# Sheet1.net
KiCad netlist of a schematic drawn in Altium Designer
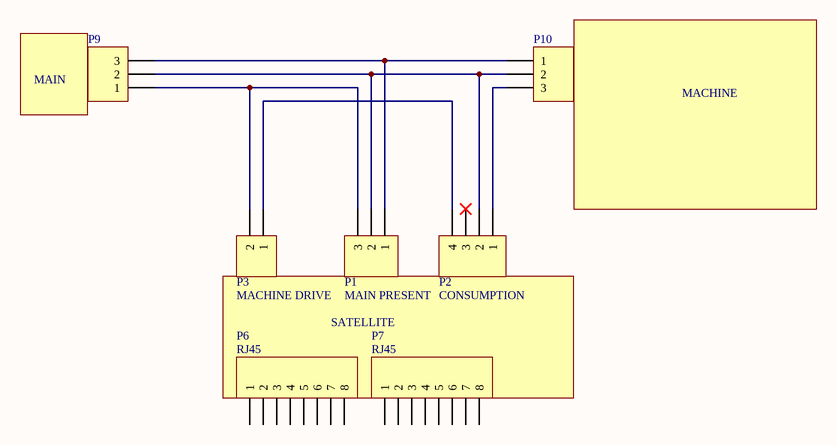
[diagram p0: Sheet1.SchDoc]

(export (version "E")
  (design (tool "Eeschema 10.0.6"))
  (components
    (comp (ref "P1")
      (value "MAIN PRESENT")
      (footprint "CO3P508")
      (description "Header, 3-Pin")
      (fields
        (field (name "MANUFACTURER") "TE CONNECTIVITY / BUCHANAN")
        (field (name "MANUFACTURER PART NUMBER") "796636-3")
      )
      (libsource (lib "Miscellaneous Connectors") (part "Header 3"))
    )
    (comp (ref "P2")
      (value "CONSUMPTION")
      (footprint "CO4P508")
      (description "Header, 4-Pin")
      (fields
        (field (name "MANUFACTURER") "TE CONNECTIVITY / BUCHANAN")
        (field (name "MANUFACTURER PART NUMBER") "796636-4")
      )
      (libsource (lib "Miscellaneous Connectors") (part "Header 4"))
    )
    (comp (ref "P3")
      (value "MACHINE DRIVE")
      (footprint "CO2P508")
      (description "Header, 2-Pin")
      (fields
        (field (name "MANUFACTURER") "TE CONNECTIVITY / BUCHANAN")
        (field (name "MANUFACTURER PART NUMBER") "796636-2")
      )
      (libsource (lib "Miscellaneous Connectors") (part "Header 2"))
    )
    (comp (ref "P6")
      (value "RJ45")
      (footprint "SYLANN:Amphenol-RJ45_8")
      (description "Header, 8-Pin")
      (fields (field (name "MANUFACTURER") "MOLEX") (field (name "MANUFACTURER PART NUMBER") "85502-5008"))
      (libsource (lib "Miscellaneous Connectors") (part "Header 8"))
    )
    (comp (ref "P7")
      (value "RJ45")
      (footprint "SYLANN:Amphenol-RJ45_8")
      (description "Header, 8-Pin")
      (fields (field (name "MANUFACTURER") "MOLEX") (field (name "MANUFACTURER PART NUMBER") "85502-5008"))
      (libsource (lib "Miscellaneous Connectors") (part "Header 8"))
    )
    (comp (ref "P9")
      (value "Header 3")
      (footprint "HDR1X3")
      (description "Header, 3-Pin")
      (fields (field (name "PUBLISHER") "Altium Limited"))
      (libsource (lib "") (part "Header 3_1"))
    )
    (comp (ref "P10")
      (value "Header 3")
      (footprint "HDR1X3")
      (description "Header, 3-Pin")
      (fields (field (name "PUBLISHER") "Altium Limited"))
      (libsource (lib "") (part "Header 3_2"))
    )
  )
  (nets
    (net (code "1") (name "Net-(P1-Pad1)") (class "Default")
      (node (ref "P1") (pin "1") (pinfunction "1_1") (pintype "passive"))
      (node (ref "P10") (pin "1") (pinfunction "1_1") (pintype "passive"))
      (node (ref "P9") (pin "3") (pinfunction "3_3") (pintype "passive"))
    )
    (net (code "2") (name "Net-(P1-Pad2)") (class "Default")
      (node (ref "P1") (pin "2") (pinfunction "2_2") (pintype "passive"))
      (node (ref "P10") (pin "2") (pinfunction "2_2") (pintype "passive"))
      (node (ref "P2") (pin "2") (pinfunction "2_2") (pintype "passive"))
      (node (ref "P9") (pin "2") (pinfunction "2_2") (pintype "passive"))
    )
    (net (code "3") (name "Net-(P1-Pad3)") (class "Default")
      (node (ref "P1") (pin "3") (pinfunction "3_3") (pintype "passive"))
      (node (ref "P3") (pin "2") (pinfunction "2_2") (pintype "passive"))
      (node (ref "P9") (pin "1") (pinfunction "1_1") (pintype "passive"))
    )
    (net (code "4") (name "Net-(P2-Pad4)") (class "Default")
      (node (ref "P2") (pin "4") (pinfunction "4_4") (pintype "passive"))
      (node (ref "P3") (pin "1") (pinfunction "1_1") (pintype "passive"))
    )
    (net (code "5") (name "Net-(P10-Pad3)") (class "Default")
      (node (ref "P10") (pin "3") (pinfunction "3_3") (pintype "passive"))
      (node (ref "P2") (pin "1") (pinfunction "1_1") (pintype "passive"))
    )
    (net (code "6") (name "unconnected-(P2-Pad3)") (class "Default")
      (node (ref "P2") (pin "3") (pinfunction "3_3") (pintype "passive+no_connect"))
    )
    (net (code "7") (name "unconnected-(P6-Pad1)") (class "Default")
      (node (ref "P6") (pin "1") (pinfunction "1_1") (pintype "passive"))
    )
    (net (code "8") (name "unconnected-(P6-Pad2)") (class "Default")
      (node (ref "P6") (pin "2") (pinfunction "2_2") (pintype "passive"))
    )
    (net (code "9") (name "unconnected-(P6-Pad3)") (class "Default")
      (node (ref "P6") (pin "3") (pinfunction "3_3") (pintype "passive"))
    )
    (net (code "10") (name "unconnected-(P6-Pad4)") (class "Default")
      (node (ref "P6") (pin "4") (pinfunction "4_4") (pintype "passive"))
    )
    (net (code "11") (name "unconnected-(P6-Pad5)") (class "Default")
      (node (ref "P6") (pin "5") (pinfunction "5_5") (pintype "passive"))
    )
    (net (code "12") (name "unconnected-(P6-Pad6)") (class "Default")
      (node (ref "P6") (pin "6") (pinfunction "6_6") (pintype "passive"))
    )
    (net (code "13") (name "unconnected-(P6-Pad7)") (class "Default")
      (node (ref "P6") (pin "7") (pinfunction "7_7") (pintype "passive"))
    )
    (net (code "14") (name "unconnected-(P6-Pad8)") (class "Default")
      (node (ref "P6") (pin "8") (pinfunction "8_8") (pintype "passive"))
    )
    (net (code "15") (name "unconnected-(P7-Pad1)") (class "Default")
      (node (ref "P7") (pin "1") (pinfunction "1_1") (pintype "passive"))
    )
    (net (code "16") (name "unconnected-(P7-Pad2)") (class "Default")
      (node (ref "P7") (pin "2") (pinfunction "2_2") (pintype "passive"))
    )
    (net (code "17") (name "unconnected-(P7-Pad3)") (class "Default")
      (node (ref "P7") (pin "3") (pinfunction "3_3") (pintype "passive"))
    )
    (net (code "18") (name "unconnected-(P7-Pad4)") (class "Default")
      (node (ref "P7") (pin "4") (pinfunction "4_4") (pintype "passive"))
    )
    (net (code "19") (name "unconnected-(P7-Pad5)") (class "Default")
      (node (ref "P7") (pin "5") (pinfunction "5_5") (pintype "passive"))
    )
    (net (code "20") (name "unconnected-(P7-Pad6)") (class "Default")
      (node (ref "P7") (pin "6") (pinfunction "6_6") (pintype "passive"))
    )
    (net (code "21") (name "unconnected-(P7-Pad7)") (class "Default")
      (node (ref "P7") (pin "7") (pinfunction "7_7") (pintype "passive"))
    )
    (net (code "22") (name "unconnected-(P7-Pad8)") (class "Default")
      (node (ref "P7") (pin "8") (pinfunction "8_8") (pintype "passive"))
    )
  )
)
